# hat.net
KiCad netlist of a schematic drawn in Altium Designer
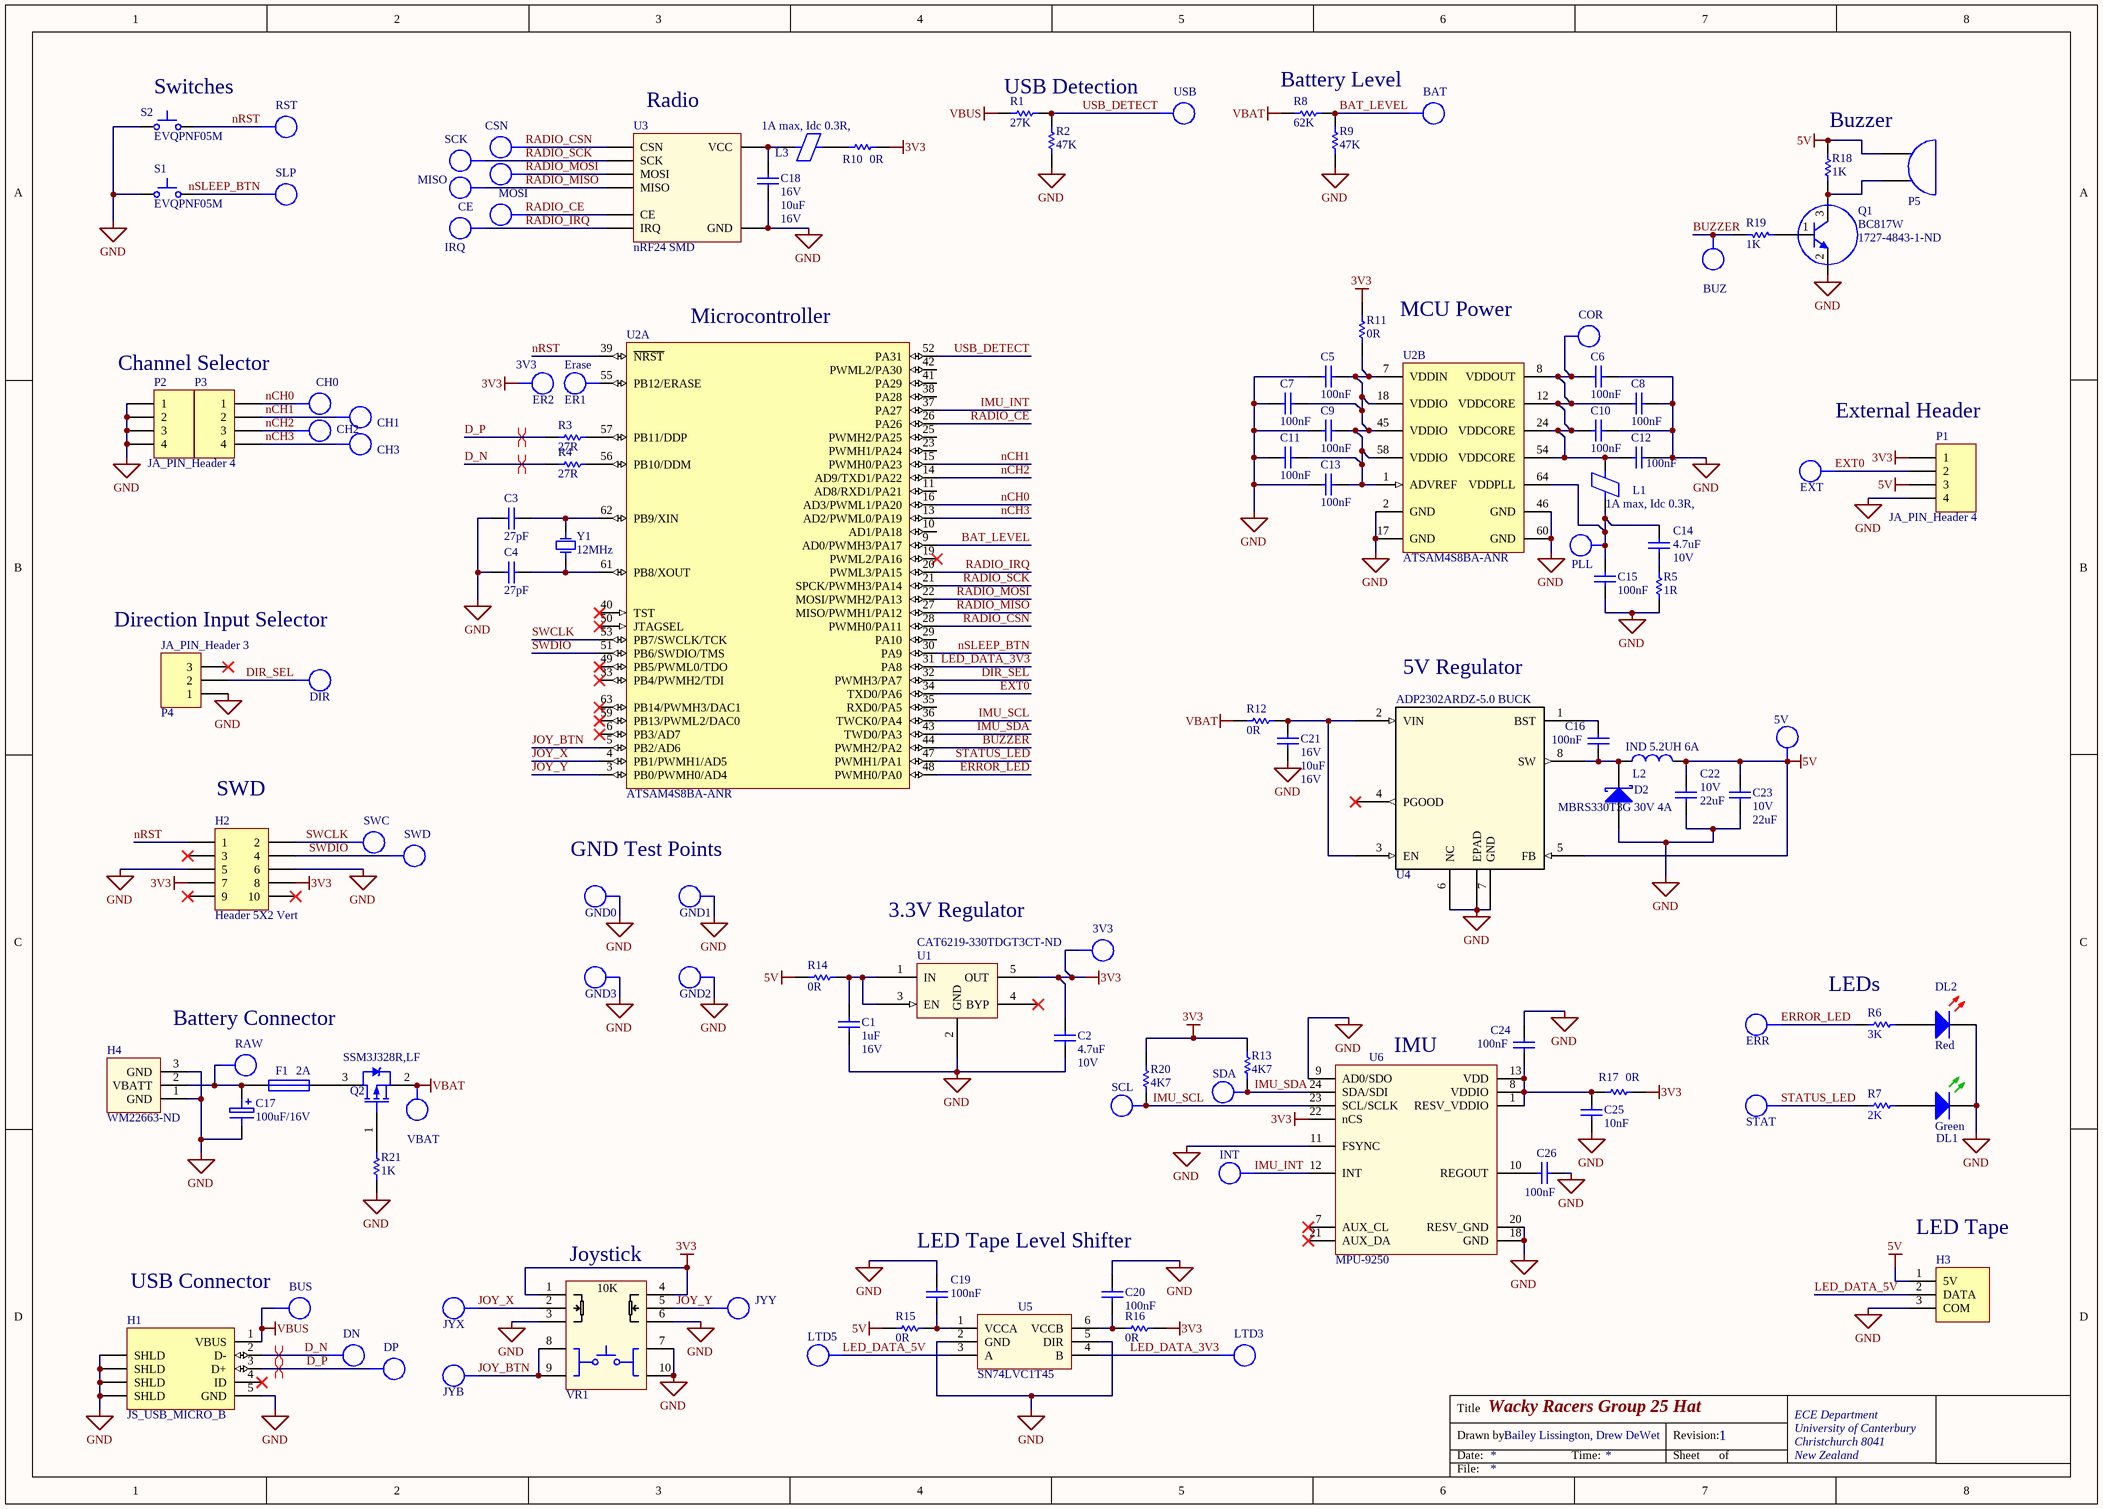
[diagram p0: hat.SchDoc]

(export (version "E")
  (design (tool "Eeschema 10.0.6"))
  (components
    (comp (ref "3V3")
      (value "3V3")
      (footprint "TP_0603")
      (description "Test-Point 3.3x1.6x2.1mm SMD")
      (fields
        (field (name "MANUFACTURER") "Harwin Inc")
        (field (name "MANUFACTURER PART NUMBER") "S1751-46R")
      )
      (libsource (lib "") (part "TP_1206_1"))
    )
    (comp (ref "5V")
      (value "3V3")
      (footprint "TP_0603")
      (description "Test-Point 3.3x1.6x2.1mm SMD")
      (fields
        (field (name "MANUFACTURER") "Harwin Inc")
        (field (name "MANUFACTURER PART NUMBER") "S1751-46R")
      )
      (libsource (lib "") (part "TP_1206_1"))
    )
    (comp (ref "BAT")
      (value "3V3")
      (footprint "TP_0603")
      (description "Test-Point 3.3x1.6x2.1mm SMD")
      (fields
        (field (name "MANUFACTURER") "Harwin Inc")
        (field (name "MANUFACTURER PART NUMBER") "S1751-46R")
      )
      (libsource (lib "") (part "TP_1206_1"))
    )
    (comp (ref "BUS")
      (value "3V3")
      (footprint "TP_0603")
      (description "Test-Point 3.3x1.6x2.1mm SMD")
      (fields
        (field (name "MANUFACTURER") "Harwin Inc")
        (field (name "MANUFACTURER PART NUMBER") "S1751-46R")
      )
      (libsource (lib "") (part "TP_1206_1"))
    )
    (comp (ref "BUZ")
      (value "3V3")
      (footprint "TP_0603")
      (description "Test-Point 3.3x1.6x2.1mm SMD")
      (fields
        (field (name "MANUFACTURER") "Harwin Inc")
        (field (name "MANUFACTURER PART NUMBER") "S1751-46R")
      )
      (libsource (lib "ECE AD19Components_22V1") (part "TP_1206"))
    )
    (comp (ref "C1")
      (value "1uF")
      (footprint "CAPC1608L")
      (description "CAP CER 1uF Y5V -20% +80% 16V 0603")
      (fields (field (name "MAX VOLTAGE") "16V"))
      (libsource (lib "ECE AD19Components_22V1") (part "CC_1uF_0603"))
    )
    (comp (ref "C2")
      (value "4.7uF")
      (footprint "CAPC1608N")
      (description "CAP CER 4.7uF X5R +-20%  10V 0603")
      (fields (field (name "MAX VOLTAGE") "10V"))
      (libsource (lib "ECE AD19Components_22V1") (part "CC_4.7uF_0603"))
    )
    (comp (ref "C3")
      (value "27pF")
      (footprint "CAPC1608L")
      (description "CAP CER 27pF NPO/COG +-5% 50V 0603")
      (libsource (lib "ECE AD19Components_22V1") (part "CC_27pF_0603"))
    )
    (comp (ref "C4")
      (value "27pF")
      (footprint "CAPC1608L")
      (description "CAP CER 27pF NPO/COG +-5% 50V 0603")
      (libsource (lib "ECE AD19Components_22V1") (part "CC_27pF_0603"))
    )
    (comp (ref "C5")
      (value "100nF")
      (footprint "CAPC1608L")
      (description "CAP CER 100nF X7R +-10% 50V 0603")
      (libsource (lib "ECE AD19Components_22V1") (part "CC_100nF_0603"))
    )
    (comp (ref "C6")
      (value "100nF")
      (footprint "CAPC1608L")
      (description "CAP CER 100nF X7R +-10% 50V 0603")
      (libsource (lib "ECE AD19Components_22V1") (part "CC_100nF_0603"))
    )
    (comp (ref "C7")
      (value "100nF")
      (footprint "CAPC1608L")
      (description "CAP CER 100nF X7R +-10% 50V 0603")
      (libsource (lib "ECE AD19Components_22V1") (part "CC_100nF_0603"))
    )
    (comp (ref "C8")
      (value "100nF")
      (footprint "CAPC1608L")
      (description "CAP CER 100nF X7R +-10% 50V 0603")
      (libsource (lib "ECE AD19Components_22V1") (part "CC_100nF_0603"))
    )
    (comp (ref "C9")
      (value "100nF")
      (footprint "CAPC1608L")
      (description "CAP CER 100nF X7R +-10% 50V 0603")
      (libsource (lib "ECE AD19Components_22V1") (part "CC_100nF_0603"))
    )
    (comp (ref "C10")
      (value "100nF")
      (footprint "CAPC1608L")
      (description "CAP CER 100nF X7R +-10% 50V 0603")
      (libsource (lib "ECE AD19Components_22V1") (part "CC_100nF_0603"))
    )
    (comp (ref "C11")
      (value "100nF")
      (footprint "CAPC1608L")
      (description "CAP CER 100nF X7R +-10% 50V 0603")
      (libsource (lib "ECE AD19Components_22V1") (part "CC_100nF_0603"))
    )
    (comp (ref "C12")
      (value "100nF")
      (footprint "CAPC1608L")
      (description "CAP CER 100nF X7R +-10% 50V 0603")
      (libsource (lib "ECE AD19Components_22V1") (part "CC_100nF_0603"))
    )
    (comp (ref "C13")
      (value "100nF")
      (footprint "CAPC1608L")
      (description "CAP CER 100nF X7R +-10% 50V 0603")
      (libsource (lib "ECE AD19Components_22V1") (part "CC_100nF_0603"))
    )
    (comp (ref "C14")
      (value "4.7uF")
      (footprint "CAPC1608N")
      (description "CAP CER 4.7uF X5R +-20%  10V 0603")
      (fields (field (name "MAX VOLTAGE") "10V"))
      (libsource (lib "ECE AD19Components_22V1") (part "CC_4.7uF_0603"))
    )
    (comp (ref "C15")
      (value "100nF")
      (footprint "CAPC1608L")
      (description "CAP CER 100nF X7R +-10% 50V 0603")
      (libsource (lib "ECE AD19Components_22V1") (part "CC_100nF_0603"))
    )
    (comp (ref "C16")
      (value "100nF")
      (footprint "CAPC1608L")
      (description "CAP CER 100nF X7R +-10% 50V 0603")
      (libsource (lib "ECE AD19Components_22V1") (part "CC_100nF_0603"))
    )
    (comp (ref "C17")
      (value "100uF/16V")
      (footprint "NICH-1")
      (description "CAP ALUM 100uF 16V SMD")
      (fields (field (name "MANUFACTURER") "Nichcon"))
      (libsource (lib "ECE AD19Components_22V1") (part "CA_100uF_16V"))
    )
    (comp (ref "C18")
      (value "10uF")
      (footprint "CAPC2012L")
      (description "CAP CER 10uF X5R 16V 0805")
      (fields
        (field (name "MANUFACTURER") "Samsung Electro-Mechanics")
        (field (name "MANUFACTURER PART NUMBER") "CL21A106KOQNNWE")
        (field (name "VOLTAGE - RATED") "16V")
        (field (name "MAX VOLTAGE") "16V")
      )
      (libsource (lib "ECE AD19Components_22V1") (part "CC_10uF_0805_16V"))
    )
    (comp (ref "C19")
      (value "100nF")
      (footprint "CAPC1608L")
      (description "CAP CER 100nF X7R +-10% 50V 0603")
      (libsource (lib "ECE AD19Components_22V1") (part "CC_100nF_0603"))
    )
    (comp (ref "C20")
      (value "100nF")
      (footprint "CAPC1608L")
      (description "CAP CER 100nF X7R +-10% 50V 0603")
      (libsource (lib "ECE AD19Components_22V1") (part "CC_100nF_0603"))
    )
    (comp (ref "C21")
      (value "10uF")
      (footprint "CAPC2012L")
      (description "CAP CER 10uF X5R 16V 0805")
      (fields
        (field (name "MANUFACTURER") "Samsung Electro-Mechanics")
        (field (name "MANUFACTURER PART NUMBER") "CL21A106KOQNNWE")
        (field (name "VOLTAGE - RATED") "16V")
        (field (name "MAX VOLTAGE") "16V")
      )
      (libsource (lib "ECE AD19Components_22V1") (part "CC_10uF_0805_16V"))
    )
    (comp (ref "C22")
      (value "22uF")
      (footprint "CAPC3216L")
      (description "CAP CER 22uF Y5V -20% +80% 10V 1206")
      (fields (field (name "MAX VOLTAGE") "10V"))
      (libsource (lib "ECE AD19Components_22V1") (part "CC_22uF_1206"))
    )
    (comp (ref "C23")
      (value "22uF")
      (footprint "CAPC3216L")
      (description "CAP CER 22uF Y5V -20% +80% 10V 1206")
      (fields (field (name "MAX VOLTAGE") "10V"))
      (libsource (lib "ECE AD19Components_22V1") (part "CC_22uF_1206"))
    )
    (comp (ref "C24")
      (value "100nF")
      (footprint "CAPC1608L")
      (description "CAP CER 100nF X7R +-10% 50V 0603")
      (libsource (lib "ECE AD19Components_22V1") (part "CC_100nF_0603"))
    )
    (comp (ref "C25")
      (value "10nF")
      (footprint "CAPC1608L")
      (description "CAP CER 10nF X7R +-10% 50V 0603")
      (libsource (lib "ECE AD19Components_22V1") (part "CC_10nF_0603"))
    )
    (comp (ref "C26")
      (value "100nF")
      (footprint "CAPC1608L")
      (description "CAP CER 100nF X7R +-10% 50V 0603")
      (libsource (lib "ECE AD19Components_22V1") (part "CC_100nF_0603"))
    )
    (comp (ref "CE")
      (value "3V3")
      (footprint "TP_0603")
      (description "Test-Point 3.3x1.6x2.1mm SMD")
      (fields
        (field (name "MANUFACTURER") "Harwin Inc")
        (field (name "MANUFACTURER PART NUMBER") "S1751-46R")
      )
      (libsource (lib "ECE AD19Components_22V1") (part "TP_1206"))
    )
    (comp (ref "CH0")
      (value "3V3")
      (footprint "TP_0603")
      (description "Test-Point 3.3x1.6x2.1mm SMD")
      (fields
        (field (name "MANUFACTURER") "Harwin Inc")
        (field (name "MANUFACTURER PART NUMBER") "S1751-46R")
      )
      (libsource (lib "ECE AD19Components_22V1") (part "TP_1206"))
    )
    (comp (ref "CH1")
      (value "3V3")
      (footprint "TP_0603")
      (description "Test-Point 3.3x1.6x2.1mm SMD")
      (fields
        (field (name "MANUFACTURER") "Harwin Inc")
        (field (name "MANUFACTURER PART NUMBER") "S1751-46R")
      )
      (libsource (lib "ECE AD19Components_22V1") (part "TP_1206"))
    )
    (comp (ref "CH2")
      (value "3V3")
      (footprint "TP_0603")
      (description "Test-Point 3.3x1.6x2.1mm SMD")
      (fields
        (field (name "MANUFACTURER") "Harwin Inc")
        (field (name "MANUFACTURER PART NUMBER") "S1751-46R")
      )
      (libsource (lib "ECE AD19Components_22V1") (part "TP_1206"))
    )
    (comp (ref "CH3")
      (value "3V3")
      (footprint "TP_0603")
      (description "Test-Point 3.3x1.6x2.1mm SMD")
      (fields
        (field (name "MANUFACTURER") "Harwin Inc")
        (field (name "MANUFACTURER PART NUMBER") "S1751-46R")
      )
      (libsource (lib "ECE AD19Components_22V1") (part "TP_1206"))
    )
    (comp (ref "COR")
      (value "3V3")
      (footprint "TP_0603")
      (description "Test-Point 3.3x1.6x2.1mm SMD")
      (fields
        (field (name "MANUFACTURER") "Harwin Inc")
        (field (name "MANUFACTURER PART NUMBER") "S1751-46R")
      )
      (libsource (lib "") (part "TP_1206_1"))
    )
    (comp (ref "CSN")
      (value "3V3")
      (footprint "TP_0603")
      (description "Test-Point 3.3x1.6x2.1mm SMD")
      (fields
        (field (name "MANUFACTURER") "Harwin Inc")
        (field (name "MANUFACTURER PART NUMBER") "S1751-46R")
      )
      (libsource (lib "ECE AD19Components_22V1") (part "TP_1206"))
    )
    (comp (ref "D2")
      (value "MBRS330T3G 30V 4A")
      (footprint "SMC")
      (description "SCHOTTKY  30V 4A")
      (fields
        (field (name "MANUFACTURER") "ON Semiconductor")
        (field (name "MANUFACTURER PART NUMBER") "MBRS330T3G")
      )
      (libsource (lib "ENCE461AD19_V22") (part "MBRS330T3G"))
    )
    (comp (ref "DIR")
      (value "3V3")
      (footprint "TP_0603")
      (description "Test-Point 3.3x1.6x2.1mm SMD")
      (fields
        (field (name "MANUFACTURER") "Harwin Inc")
        (field (name "MANUFACTURER PART NUMBER") "S1751-46R")
      )
      (libsource (lib "ECE AD19Components_22V1") (part "TP_1206"))
    )
    (comp (ref "DL1")
      (value "Green")
      (footprint "WL-SMCW0603")
      (description "LED Green 430mcd 0603 SMD")
      (fields
        (field (name "MANUFACTURER") "WURTH ELEKTRONIK")
        (field (name "MANUFACTURER PART NUMBER") "150060GS75000")
        (field (name "LED COLOUR") "Green")
      )
      (libsource (lib "ECE AD19Components_22V1") (part "DL_150060GS75000"))
    )
    (comp (ref "DL2")
      (value "Red")
      (footprint "WL-SMCW0603")
      (description "LED Red 250mcd 0603 SMD")
      (fields
        (field (name "MANUFACTURER") "WURTH ELEKTRONIK")
        (field (name "MANUFACTURER PART NUMBER") "150060RS75000")
        (field (name "LED COLOUR") "Red")
      )
      (libsource (lib "ECE AD19Components_22V1") (part "DL_150060RS75000"))
    )
    (comp (ref "DN")
      (value "3V3")
      (footprint "TP_0603")
      (description "Test-Point 3.3x1.6x2.1mm SMD")
      (fields
        (field (name "MANUFACTURER") "Harwin Inc")
        (field (name "MANUFACTURER PART NUMBER") "S1751-46R")
      )
      (libsource (lib "") (part "TP_1206_1"))
    )
    (comp (ref "DP")
      (value "3V3")
      (footprint "TP_0603")
      (description "Test-Point 3.3x1.6x2.1mm SMD")
      (fields
        (field (name "MANUFACTURER") "Harwin Inc")
        (field (name "MANUFACTURER PART NUMBER") "S1751-46R")
      )
      (libsource (lib "") (part "TP_1206_1"))
    )
    (comp (ref "ER1")
      (value "Erase")
      (footprint "TP_0603")
      (description "Test-Point 3.3x1.6x2.1mm SMD")
      (fields
        (field (name "MANUFACTURER") "Harwin Inc")
        (field (name "MANUFACTURER PART NUMBER") "S1751-46R")
      )
      (libsource (lib "") (part "TP_1206_1"))
    )
    (comp (ref "ER2")
      (value "3V3")
      (footprint "TP_0603")
      (description "Test-Point 3.3x1.6x2.1mm SMD")
      (fields
        (field (name "MANUFACTURER") "Harwin Inc")
        (field (name "MANUFACTURER PART NUMBER") "S1751-46R")
      )
      (libsource (lib "") (part "TP_1206_1"))
    )
    (comp (ref "ERR")
      (value "3V3")
      (footprint "TP_0603")
      (description "Test-Point 3.3x1.6x2.1mm SMD")
      (fields
        (field (name "MANUFACTURER") "Harwin Inc")
        (field (name "MANUFACTURER PART NUMBER") "S1751-46R")
      )
      (libsource (lib "ECE AD19Components_22V1") (part "TP_1206"))
    )
    (comp (ref "EXT")
      (value "3V3")
      (footprint "TP_0603")
      (description "Test-Point 3.3x1.6x2.1mm SMD")
      (fields
        (field (name "MANUFACTURER") "Harwin Inc")
        (field (name "MANUFACTURER PART NUMBER") "S1751-46R")
      )
      (libsource (lib "") (part "TP_1206_1"))
    )
    (comp (ref "F1")
      (value "2A")
      (footprint "RESC3216N")
      (description "Fuse 2.0A Very Fast Acting 1206 SMD")
      (fields
        (field (name "MANUFACTURER") "MULTICOMP")
        (field (name "MANUFACTURER PART NUMBER") "MC12CF 002")
      )
      (libsource (lib "ECE AD19Components_22V1") (part "FS_Fuse_2.0A"))
    )
    (comp (ref "GND0")
      (value "TP")
      (footprint "TP_1206")
      (description "Test-Point 3.3x1.6x2.1mm SMD")
      (fields
        (field (name "MANUFACTURER") "Harwin Inc")
        (field (name "MANUFACTURER PART NUMBER") "S1751-46R")
      )
      (libsource (lib "") (part "TP_1206_1"))
    )
    (comp (ref "GND1")
      (value "TP")
      (footprint "TP_1206")
      (description "Test-Point 3.3x1.6x2.1mm SMD")
      (fields
        (field (name "MANUFACTURER") "Harwin Inc")
        (field (name "MANUFACTURER PART NUMBER") "S1751-46R")
      )
      (libsource (lib "") (part "TP_1206_1"))
    )
    (comp (ref "GND2")
      (value "TP")
      (footprint "TP_1206")
      (description "Test-Point 3.3x1.6x2.1mm SMD")
      (fields
        (field (name "MANUFACTURER") "Harwin Inc")
        (field (name "MANUFACTURER PART NUMBER") "S1751-46R")
      )
      (libsource (lib "") (part "TP_1206_1"))
    )
    (comp (ref "GND3")
      (value "TP")
      (footprint "TP_1206")
      (description "Test-Point 3.3x1.6x2.1mm SMD")
      (fields
        (field (name "MANUFACTURER") "Harwin Inc")
        (field (name "MANUFACTURER PART NUMBER") "S1751-46R")
      )
      (libsource (lib "") (part "TP_1206_1"))
    )
    (comp (ref "H1")
      (value "JS_USB_MICRO_B")
      (footprint "FCI_USB_10118194-0001LF")
      (description "CONN USB MICRO B RECPT SMT R/A")
      (fields (field (name "MANUFACTURER") "FCI") (field (name "MANUFACTURER PART NUMBER") "10118194-0001LF"))
      (libsource (lib "ECE AD19Components_22V1") (part "JS_USB_MICRO_B_SMT"))
    )
    (comp (ref "H2")
      (value "Header 5X2 Vert")
      (footprint "IDC2.54-V10D")
      (description "IDC Header, 2,54mm, 10-Pin, Vert")
      (libsource (lib "ECE AD19Components_22V1") (part "JA_HDR_IDC_5X2_VERT"))
    )
    (comp (ref "H3")
      (value "3 Pin Molex KK Hdr")
      (footprint "MOLEX_KK_3_HDR")
      (description "CONN HEADER 3POS 2.54mm VERT_Thru Hole")
      (fields (field (name "MANUFACTURER") "Molex"))
      (libsource (lib "ENCE461AD19_V22") (part "LED_Strip_Header"))
    )
    (comp (ref "H4")
      (value "Battery_HEADER_3pin")
      (footprint "BATT_HEADER_3POS")
      (description "3Pin Header 2.54mm spacing\r\nDigikey #WM22663-ND")
      (fields (field (name "SUPPLIER PART NUMBER 1") "WM22663-ND"))
      (libsource (lib "ENCE461AD19_V22") (part "Battery_HEADER_3pin"))
    )
    (comp (ref "INT")
      (value "3V3")
      (footprint "TP_0603")
      (description "Test-Point 3.3x1.6x2.1mm SMD")
      (fields
        (field (name "MANUFACTURER") "Harwin Inc")
        (field (name "MANUFACTURER PART NUMBER") "S1751-46R")
      )
      (libsource (lib "ECE AD19Components_22V1") (part "TP_1206"))
    )
    (comp (ref "IRQ")
      (value "3V3")
      (footprint "TP_0603")
      (description "Test-Point 3.3x1.6x2.1mm SMD")
      (fields
        (field (name "MANUFACTURER") "Harwin Inc")
        (field (name "MANUFACTURER PART NUMBER") "S1751-46R")
      )
      (libsource (lib "ECE AD19Components_22V1") (part "TP_1206"))
    )
    (comp (ref "JYB")
      (value "3V3")
      (footprint "TP_0603")
      (description "Test-Point 3.3x1.6x2.1mm SMD")
      (fields
        (field (name "MANUFACTURER") "Harwin Inc")
        (field (name "MANUFACTURER PART NUMBER") "S1751-46R")
      )
      (libsource (lib "") (part "TP_1206_1"))
    )
    (comp (ref "JYX")
      (value "3V3")
      (footprint "TP_0603")
      (description "Test-Point 3.3x1.6x2.1mm SMD")
      (fields
        (field (name "MANUFACTURER") "Harwin Inc")
        (field (name "MANUFACTURER PART NUMBER") "S1751-46R")
      )
      (libsource (lib "") (part "TP_1206_1"))
    )
    (comp (ref "JYY")
      (value "3V3")
      (footprint "TP_0603")
      (description "Test-Point 3.3x1.6x2.1mm SMD")
      (fields
        (field (name "MANUFACTURER") "Harwin Inc")
        (field (name "MANUFACTURER PART NUMBER") "S1751-46R")
      )
      (libsource (lib "ECE AD19Components_22V1") (part "TP_1206"))
    )
    (comp (ref "L1")
      (value "1A max, Idc 0.3R,")
      (footprint "INDC3216L")
      (description "Ferrite Bead, Rdc 0.3R, Z100MHZ 600R, Imax 1A, SMD 1206")
      (fields
        (field (name "MANUFACTURER") "FAIR-RITE")
        (field (name "MANUFACTURER PART NUMBER") "2512066017Y1")
      )
      (libsource (lib "ECE AD19Components_22V1") (part "IN_Ferrite-Bead"))
    )
    (comp (ref "L2")
      (value "IND 5.2UH 6A")
      (footprint "INDUCTOR5u2")
      (description "FIXED IND 5.2UH 6A 22 MOHM SMD")
      (fields
        (field (name "MANUFACTURER") "Sumida America Components Inc.")
        (field (name "MANUFACTURER PART NUMBER") "CDRH104RNP-5R2NC")
      )
      (libsource (lib "ENCE461AD19_V22") (part "CDRH104RNP-5R2NC"))
    )
    (comp (ref "L3")
      (value "1A max, Idc 0.3R,")
      (footprint "INDC3216L")
      (description "Ferrite Bead, Rdc 0.3R, Z100MHZ 600R, Imax 1A, SMD 1206")
      (fields
        (field (name "MANUFACTURER") "FAIR-RITE")
        (field (name "MANUFACTURER PART NUMBER") "2512066017Y1")
      )
      (libsource (lib "ECE AD19Components_22V1") (part "IN_Ferrite-Bead"))
    )
    (comp (ref "LTD3")
      (value "3V3")
      (footprint "TP_0603")
      (description "Test-Point 3.3x1.6x2.1mm SMD")
      (fields
        (field (name "MANUFACTURER") "Harwin Inc")
        (field (name "MANUFACTURER PART NUMBER") "S1751-46R")
      )
      (libsource (lib "") (part "TP_1206_1"))
    )
    (comp (ref "LTD5")
      (value "3V3")
      (footprint "TP_0603")
      (description "Test-Point 3.3x1.6x2.1mm SMD")
      (fields
        (field (name "MANUFACTURER") "Harwin Inc")
        (field (name "MANUFACTURER PART NUMBER") "S1751-46R")
      )
      (libsource (lib "ECE AD19Components_22V1") (part "TP_1206"))
    )
    (comp (ref "MISO")
      (value "3V3")
      (footprint "TP_0603")
      (description "Test-Point 3.3x1.6x2.1mm SMD")
      (fields
        (field (name "MANUFACTURER") "Harwin Inc")
        (field (name "MANUFACTURER PART NUMBER") "S1751-46R")
      )
      (libsource (lib "ECE AD19Components_22V1") (part "TP_1206"))
    )
    (comp (ref "MOSI")
      (value "3V3")
      (footprint "TP_0603")
      (description "Test-Point 3.3x1.6x2.1mm SMD")
      (fields
        (field (name "MANUFACTURER") "Harwin Inc")
        (field (name "MANUFACTURER PART NUMBER") "S1751-46R")
      )
      (libsource (lib "ECE AD19Components_22V1") (part "TP_1206"))
    )
    (comp (ref "P1")
      (value "JA_PIN_Header 4")
      (footprint "HDR1X4")
      (description "Header, 4-Pin")
      (fields (field (name "PUBLISHER") "Altium Limited"))
      (libsource (lib "") (part "JA_PIN_Header 4_1"))
    )
    (comp (ref "P2")
      (value "JA_PIN_Header 4")
      (footprint "HDR1X4")
      (description "Header, 4-Pin")
      (fields (field (name "PUBLISHER") "Altium Limited"))
      (libsource (lib "") (part "JA_PIN_Header 4_1"))
    )
    (comp (ref "P3")
      (value "JA_PIN_Header 4")
      (footprint "HDR1X4")
      (description "Header, 4-Pin")
      (fields (field (name "PUBLISHER") "Altium Limited"))
      (libsource (lib "ECE AD19Components_22V1") (part "JA_PIN_Header 4"))
    )
    (comp (ref "P4")
      (value "JA_PIN_Header 3")
      (footprint "HDR1X3")
      (description "Header, 3-Pin")
      (fields (field (name "PUBLISHER") "Altium Limited"))
      (libsource (lib "ECE AD19Components_22V1") (part "JA_PIN_Header 3"))
    )
    (comp (ref "P5")
      (value "Piezo Buzzer")
      (footprint "BUZZER")
      (description "TDK - PS1240P02BT - BUZZER, PIEZO, 70DB, 12.2MM")
      (libsource (lib "ENCE461AD19_V22") (part "Piezo Buzzer"))
    )
    (comp (ref "PLL")
      (value "3V3")
      (footprint "TP_0603")
      (description "Test-Point 3.3x1.6x2.1mm SMD")
      (fields
        (field (name "MANUFACTURER") "Harwin Inc")
        (field (name "MANUFACTURER PART NUMBER") "S1751-46R")
      )
      (libsource (lib "") (part "TP_1206_1"))
    )
    (comp (ref "Q1")
      (value "BC817W")
      (footprint "SOT323_M")
      (description "NPN GP Bipolar Transistor 45V 500mA SOT323")
      (fields (field (name "MANUFACTURER") "NXP") (field (name "SUPPLIER PART NUMBER 2") "1727-4843-1-ND"))
      (libsource (lib "ECE AD19Components_22V1") (part "TB_BC817W"))
    )
    (comp (ref "Q2")
      (value "SSM3J328R,LF")
      (footprint "SOT23_L")
      (description "MOSFET P-CH 20V 6A SOT23-3")
      (fields
        (field (name "MANUFACTURER") "Toshiba")
        (field (name "MANUFACTURER PART NUMBER") "SSM3J328R,LF")
      )
      (libsource (lib "ECE AD19Components_22V1") (part "TM_SSM3J328R"))
    )
    (comp (ref "R1")
      (value "27K")
      (footprint "RESC1608L")
      (description "RES 27K OHM 1/10W 5% 0603 SMD")
      (libsource (lib "ECE AD19Components_22V1") (part "RS_27K"))
    )
    (comp (ref "R2")
      (value "47K")
      (footprint "RESC1608N")
      (description "RES 47.0K OHM 1/10W 5% 0603 SMD")
      (libsource (lib "ECE AD19Components_22V1") (part "RS_47K"))
    )
    (comp (ref "R3")
      (value "27R")
      (footprint "RESC1608L")
      (description "RES 27 OHM 1/10W 5% 0603 SMD")
      (libsource (lib "ECE AD19Components_22V1") (part "RS_27R"))
    )
    (comp (ref "R4")
      (value "27R")
      (footprint "RESC1608L")
      (description "RES 27 OHM 1/10W 5% 0603 SMD")
      (libsource (lib "ECE AD19Components_22V1") (part "RS_27R"))
    )
    (comp (ref "R5")
      (value "1R")
      (footprint "RESC3216L")
      (description "RES 1R OHM 1/4W 5% 1206 SMD")
      (libsource (lib "ECE AD19Components_22V1") (part "RT_1R"))
    )
    (comp (ref "R6")
      (value "3K")
      (footprint "RESC1608L")
      (description "RES 3K OHM 1/10W 5% 0603 SMD")
      (libsource (lib "ECE AD19Components_22V1") (part "RS_3K"))
    )
    (comp (ref "R7")
      (value "2K")
      (footprint "RESC1608L")
      (description "RES 2K OHM 1/10W 5% 0603 SMD")
      (libsource (lib "ECE AD19Components_22V1") (part "RS_2K"))
    )
    (comp (ref "R8")
      (value "62K")
      (footprint "RESC1608L")
      (description "RES 62.0K OHM 1/10W 5% 0603 SMD")
      (libsource (lib "ECE AD19Components_22V1") (part "RS_62K"))
    )
    (comp (ref "R9")
      (value "47K")
      (footprint "RESC1608N")
      (description "RES 47.0K OHM 1/10W 5% 0603 SMD")
      (libsource (lib "ECE AD19Components_22V1") (part "RS_47K"))
    )
    (comp (ref "R10")
      (value "0R")
      (footprint "RESC1608L")
      (description "RES 0.0 OHM 1/10W 5% 0603 SMD")
      (libsource (lib "ECE AD19Components_22V1") (part "RS_0R0"))
    )
    (comp (ref "R11")
      (value "0R")
      (footprint "RESC1608L")
      (description "RES 0.0 OHM 1/10W 5% 0603 SMD")
      (libsource (lib "ECE AD19Components_22V1") (part "RS_0R0"))
    )
    (comp (ref "R12")
      (value "0R")
      (footprint "RESC1608L")
      (description "RES 0.0 OHM 1/10W 5% 0603 SMD")
      (libsource (lib "ECE AD19Components_22V1") (part "RS_0R0"))
    )
    (comp (ref "R13")
      (value "4K7")
      (footprint "RESC1608L")
      (description "RES 4.7K OHM 1/10W 5% 0603 SMD")
      (libsource (lib "ECE AD19Components_22V1") (part "RS_4K7"))
    )
    (comp (ref "R14")
      (value "0R")
      (footprint "RESC1608L")
      (description "RES 0.0 OHM 1/10W 5% 0603 SMD")
      (libsource (lib "ECE AD19Components_22V1") (part "RS_0R0"))
    )
    (comp (ref "R15")
      (value "0R")
      (footprint "RESC1608L")
      (description "RES 0.0 OHM 1/10W 5% 0603 SMD")
      (libsource (lib "ECE AD19Components_22V1") (part "RS_0R0"))
    )
    (comp (ref "R16")
      (value "0R")
      (footprint "RESC1608L")
      (description "RES 0.0 OHM 1/10W 5% 0603 SMD")
      (libsource (lib "ECE AD19Components_22V1") (part "RS_0R0"))
    )
    (comp (ref "R17")
      (value "0R")
      (footprint "RESC1608L")
      (description "RES 0.0 OHM 1/10W 5% 0603 SMD")
      (libsource (lib "ECE AD19Components_22V1") (part "RS_0R0"))
    )
    (comp (ref "R18")
      (value "1K")
      (footprint "RESC1608L")
      (description "RES 1.0K OHM 1/10W 5% 0603 SMD")
      (libsource (lib "ECE AD19Components_22V1") (part "RS_1K"))
    )
    (comp (ref "R19")
      (value "1K")
      (footprint "RESC1608L")
      (description "RES 1.0K OHM 1/10W 5% 0603 SMD")
      (libsource (lib "ECE AD19Components_22V1") (part "RS_1K"))
    )
    (comp (ref "R20")
      (value "4K7")
      (footprint "RESC1608L")
      (description "RES 4.7K OHM 1/10W 5% 0603 SMD")
      (libsource (lib "ECE AD19Components_22V1") (part "RS_4K7"))
    )
    (comp (ref "R21")
      (value "1K")
      (footprint "RESC1608L")
      (description "RES 1.0K OHM 1/10W 5% 0603 SMD")
      (libsource (lib "ECE AD19Components_22V1") (part "RS_1K"))
    )
    (comp (ref "RAW")
      (value "3V3")
      (footprint "TP_0603")
      (description "Test-Point 3.3x1.6x2.1mm SMD")
      (fields
        (field (name "MANUFACTURER") "Harwin Inc")
        (field (name "MANUFACTURER PART NUMBER") "S1751-46R")
      )
      (libsource (lib "") (part "TP_1206_1"))
    )
    (comp (ref "RST")
      (value "3V3")
      (footprint "TP_0603")
      (description "Test-Point 3.3x1.6x2.1mm SMD")
      (fields
        (field (name "MANUFACTURER") "Harwin Inc")
        (field (name "MANUFACTURER PART NUMBER") "S1751-46R")
      )
      (libsource (lib "") (part "TP_1206_1"))
    )
    (comp (ref "S1")
      (value "EVQPNF05M")
      (footprint "EVQPNF05M")
      (description "Panasonic 6 x 3.5mm SMD Light Touch Switch Type SMD")
      (fields (field (name "MANUFACTURER") "Panasonic"))
      (libsource (lib "ECE AD19Components_22V1") (part "WS_EVQPNF05M"))
    )
    (comp (ref "S2")
      (value "EVQPNF05M")
      (footprint "EVQPNF05M")
      (description "Panasonic 6 x 3.5mm SMD Light Touch Switch Type SMD")
      (fields (field (name "MANUFACTURER") "Panasonic"))
      (libsource (lib "ECE AD19Components_22V1") (part "WS_EVQPNF05M"))
    )
    (comp (ref "SCK")
      (value "3V3")
      (footprint "TP_0603")
      (description "Test-Point 3.3x1.6x2.1mm SMD")
      (fields
        (field (name "MANUFACTURER") "Harwin Inc")
        (field (name "MANUFACTURER PART NUMBER") "S1751-46R")
      )
      (libsource (lib "ECE AD19Components_22V1") (part "TP_1206"))
    )
    (comp (ref "SCL")
      (value "3V3")
      (footprint "TP_0603")
      (description "Test-Point 3.3x1.6x2.1mm SMD")
      (fields
        (field (name "MANUFACTURER") "Harwin Inc")
        (field (name "MANUFACTURER PART NUMBER") "S1751-46R")
      )
      (libsource (lib "ECE AD19Components_22V1") (part "TP_1206"))
    )
    (comp (ref "SDA")
      (value "3V3")
      (footprint "TP_0603")
      (description "Test-Point 3.3x1.6x2.1mm SMD")
      (fields
        (field (name "MANUFACTURER") "Harwin Inc")
        (field (name "MANUFACTURER PART NUMBER") "S1751-46R")
      )
      (libsource (lib "ECE AD19Components_22V1") (part "TP_1206"))
    )
    (comp (ref "SLP")
      (value "3V3")
      (footprint "TP_0603")
      (description "Test-Point 3.3x1.6x2.1mm SMD")
      (fields
        (field (name "MANUFACTURER") "Harwin Inc")
        (field (name "MANUFACTURER PART NUMBER") "S1751-46R")
      )
      (libsource (lib "") (part "TP_1206_1"))
    )
    (comp (ref "STAT")
      (value "3V3")
      (footprint "TP_0603")
      (description "Test-Point 3.3x1.6x2.1mm SMD")
      (fields
        (field (name "MANUFACTURER") "Harwin Inc")
        (field (name "MANUFACTURER PART NUMBER") "S1751-46R")
      )
      (libsource (lib "ECE AD19Components_22V1") (part "TP_1206"))
    )
    (comp (ref "SWC")
      (value "3V3")
      (footprint "TP_0603")
      (description "Test-Point 3.3x1.6x2.1mm SMD")
      (fields
        (field (name "MANUFACTURER") "Harwin Inc")
        (field (name "MANUFACTURER PART NUMBER") "S1751-46R")
      )
      (libsource (lib "") (part "TP_1206_1"))
    )
    (comp (ref "SWD")
      (value "3V3")
      (footprint "TP_0603")
      (description "Test-Point 3.3x1.6x2.1mm SMD")
      (fields
        (field (name "MANUFACTURER") "Harwin Inc")
        (field (name "MANUFACTURER PART NUMBER") "S1751-46R")
      )
      (libsource (lib "") (part "TP_1206_1"))
    )
    (comp (ref "U1")
      (value "CAT6219-330TDGT3")
      (footprint "SOT95P280X145-5N")
      (description "IC REG LIN 3.3V 500MA TSOT23-5")
      (fields
        (field (name "BASE PART NUMBER") "CAT6219")
        (field (name "SUPPLIER PART NUMBER") "CAT6219-330TDGT3CT-ND")
      )
      (libsource (lib "ENCE461AD19_V22") (part "SV_CAT6219-330TDGT3"))
    )
    (comp (ref "U2")
      (value "ATSAM4S8BA-ANR")
      (footprint "LQFP64_L")
      (description "IC MCU 32BIT 512KB FLASH 64LQFP")
      (fields (field (name "MANUFACTURER") "Atmel"))
      (libsource (lib "ECE AD19Components_22V1") (part "SE_ATSAM4S16BA-MU"))
    )
    (comp (ref "U3")
      (value "nRF24 SMD")
      (footprint "NRF24")
      (description "nRF24 SMD Module")
      (libsource (lib "ENCE461AD19_V22") (part "NRF24"))
    )
    (comp (ref "U4")
      (value "ADP2302ARDZ-5.0 BUCK")
      (footprint "RD_8_1")
      (description "IC REG BUCK 5V 2A 8SOIC")
      (fields (field (name "MANUFACTURER_PART_NUMBER") "ADP2302ARDZ-5.0-R7"))
      (libsource (lib "ENCE461AD19_V22") (part "ADP2302ARDZ-5.0-R7"))
    )
    (comp (ref "U5")
      (value "SN74LVC1T45")
      (footprint "SOT23-6_N")
      (description "1.8V - 5V level converter")
      (libsource (lib "ENCE461AD19_V22") (part "SN74LVC1T45"))
    )
    (comp (ref "U6")
      (value "MPU-9250")
      (footprint "Quad24")
      (description "9 axis IMU")
      (libsource (lib "ENCE461AD19_V22") (part "MPU-9250"))
    )
    (comp (ref "USB")
      (value "3V3")
      (footprint "TP_0603")
      (description "Test-Point 3.3x1.6x2.1mm SMD")
      (fields
        (field (name "MANUFACTURER") "Harwin Inc")
        (field (name "MANUFACTURER PART NUMBER") "S1751-46R")
      )
      (libsource (lib "") (part "TP_1206_1"))
    )
    (comp (ref "VBAT")
      (value "3V3")
      (footprint "TP_0603")
      (description "Test-Point 3.3x1.6x2.1mm SMD")
      (fields
        (field (name "MANUFACTURER") "Harwin Inc")
        (field (name "MANUFACTURER PART NUMBER") "S1751-46R")
      )
      (libsource (lib "") (part "TP_1206_1"))
    )
    (comp (ref "VR1")
      (value "Joystick 10k with Sw")
      (footprint "Joystick_Sw")
      (description "JOYSTICK 10K OHM 2 AXIS TH")
      (libsource (lib "ENCE461AD19_V22") (part "Joystick 10k with Sw"))
    )
    (comp (ref "Y1")
      (value "12MHz")
      (footprint "6.0X3.5-4")
      (description "CRYSTAL 12MHZ 18PF 6X3.5mm SMD")
      (fields
        (field (name "MANUFACTURER") "CTS-Frequency Controls")
        (field (name "MANUFACTURER PART NUMBER") "406C35D12M00000")
        (field (name "FREQUENCY") "12MHz")
      )
      (libsource (lib "ECE AD19Components_22V1") (part "XT_CRYSTAL_12MHz_18pF"))
    )
  )
  (nets
    (net (code "1") (name "/BAT_LEVEL") (class "Default")
      (node (ref "BAT") (pin "1") (pinfunction "1_1") (pintype "passive"))
      (node (ref "R8") (pin "1") (pinfunction "1_1") (pintype "passive"))
      (node (ref "R9") (pin "2") (pinfunction "2_2") (pintype "passive"))
      (node (ref "U2") (pin "9") (pinfunction "AD0/PWMH3/PA17_9") (pintype "bidirectional"))
    )
    (net (code "2") (name "/BUZZER") (class "Default")
      (node (ref "BUZ") (pin "1") (pinfunction "1_1") (pintype "passive"))
      (node (ref "R19") (pin "2") (pinfunction "2_2") (pintype "passive"))
      (node (ref "U2") (pin "44") (pinfunction "PWMH2/PA2_44") (pintype "bidirectional"))
    )
    (net (code "3") (name "/DIR_SEL") (class "Default")
      (node (ref "DIR") (pin "1") (pinfunction "1_1") (pintype "passive"))
      (node (ref "P4") (pin "2") (pinfunction "2_2") (pintype "passive"))
      (node (ref "U2") (pin "32") (pinfunction "PWMH3/PA7_32") (pintype "bidirectional"))
    )
    (net (code "4") (name "/D_N") (class "Default")
      (node (ref "DN") (pin "1") (pinfunction "1_1") (pintype "passive"))
      (node (ref "H1") (pin "2") (pinfunction "D-_2") (pintype "bidirectional"))
      (node (ref "R4") (pin "1") (pinfunction "1_1") (pintype "passive"))
    )
    (net (code "5") (name "/D_P") (class "Default")
      (node (ref "DP") (pin "1") (pinfunction "1_1") (pintype "passive"))
      (node (ref "H1") (pin "3") (pinfunction "D+_3") (pintype "bidirectional"))
      (node (ref "R3") (pin "1") (pinfunction "1_1") (pintype "passive"))
    )
    (net (code "6") (name "/ERROR_LED") (class "Default")
      (node (ref "ERR") (pin "1") (pinfunction "1_1") (pintype "passive"))
      (node (ref "R6") (pin "1") (pinfunction "1_1") (pintype "passive"))
      (node (ref "U2") (pin "48") (pinfunction "PWMH0/PA0_48") (pintype "bidirectional"))
    )
    (net (code "7") (name "/EXT0") (class "Default")
      (node (ref "EXT") (pin "1") (pinfunction "1_1") (pintype "passive"))
      (node (ref "P1") (pin "2") (pinfunction "2_2") (pintype "passive"))
      (node (ref "U2") (pin "34") (pinfunction "TXD0/PA6_34") (pintype "bidirectional"))
    )
    (net (code "8") (name "/IMU_INT") (class "Default")
      (node (ref "INT") (pin "1") (pinfunction "1_1") (pintype "passive"))
      (node (ref "U2") (pin "37") (pinfunction "PA27_37") (pintype "bidirectional"))
      (node (ref "U6") (pin "12") (pinfunction "INT_12") (pintype "passive"))
    )
    (net (code "9") (name "/IMU_SCL") (class "Default")
      (node (ref "R20") (pin "1") (pinfunction "1_1") (pintype "passive"))
      (node (ref "SCL") (pin "1") (pinfunction "1_1") (pintype "passive"))
      (node (ref "U2") (pin "36") (pinfunction "TWCK0/PA4_36") (pintype "bidirectional"))
      (node (ref "U6") (pin "23") (pinfunction "SCL/SCLK_23") (pintype "passive"))
    )
    (net (code "10") (name "/IMU_SDA") (class "Default")
      (node (ref "R13") (pin "1") (pinfunction "1_1") (pintype "passive"))
      (node (ref "SDA") (pin "1") (pinfunction "1_1") (pintype "passive"))
      (node (ref "U2") (pin "43") (pinfunction "TWD0/PA3_43") (pintype "bidirectional"))
      (node (ref "U6") (pin "24") (pinfunction "SDA/SDI_24") (pintype "passive"))
    )
    (net (code "11") (name "/JOY_BTN") (class "Default")
      (node (ref "JYB") (pin "1") (pinfunction "1_1") (pintype "passive"))
      (node (ref "U2") (pin "5") (pinfunction "PB2/AD6_5") (pintype "bidirectional"))
      (node (ref "VR1") (pin "8") (pinfunction "8_8") (pintype "passive"))
      (node (ref "VR1") (pin "9") (pinfunction "9_9") (pintype "passive"))
    )
    (net (code "12") (name "/JOY_X") (class "Default")
      (node (ref "JYX") (pin "1") (pinfunction "1_1") (pintype "passive"))
      (node (ref "U2") (pin "4") (pinfunction "PB1/PWMH1/AD5_4") (pintype "bidirectional"))
      (node (ref "VR1") (pin "2") (pinfunction "2_2") (pintype "passive"))
    )
    (net (code "13") (name "/JOY_Y") (class "Default")
      (node (ref "JYY") (pin "1") (pinfunction "1_1") (pintype "passive"))
      (node (ref "U2") (pin "3") (pinfunction "PB0/PWMH0/AD4_3") (pintype "bidirectional"))
      (node (ref "VR1") (pin "5") (pinfunction "2'_5") (pintype "passive"))
    )
    (net (code "14") (name "/LED_DATA_3V3") (class "Default")
      (node (ref "LTD3") (pin "1") (pinfunction "1_1") (pintype "passive"))
      (node (ref "U2") (pin "31") (pinfunction "PA8_31") (pintype "bidirectional"))
      (node (ref "U5") (pin "4") (pinfunction "B_4") (pintype "passive"))
    )
    (net (code "15") (name "/LED_DATA_5V") (class "Default")
      (node (ref "H3") (pin "2") (pinfunction "DATA_2") (pintype "passive"))
      (node (ref "LTD5") (pin "1") (pinfunction "1_1") (pintype "passive"))
      (node (ref "U5") (pin "3") (pinfunction "A_3") (pintype "passive"))
    )
    (net (code "16") (name "/RADIO_CE") (class "Default")
      (node (ref "CE") (pin "1") (pinfunction "1_1") (pintype "passive"))
      (node (ref "U2") (pin "26") (pinfunction "PA26_26") (pintype "bidirectional"))
      (node (ref "U3") (pin "3") (pinfunction "CE_3") (pintype "passive"))
    )
    (net (code "17") (name "/RADIO_CSN") (class "Default")
      (node (ref "CSN") (pin "1") (pinfunction "1_1") (pintype "passive"))
      (node (ref "U2") (pin "28") (pinfunction "PWMH0/PA11_28") (pintype "bidirectional"))
      (node (ref "U3") (pin "4") (pinfunction "CSN_4") (pintype "passive"))
    )
    (net (code "18") (name "/RADIO_IRQ") (class "Default")
      (node (ref "IRQ") (pin "1") (pinfunction "1_1") (pintype "passive"))
      (node (ref "U2") (pin "20") (pinfunction "PWML3/PA15_20") (pintype "bidirectional"))
      (node (ref "U3") (pin "8") (pinfunction "IRQ_8") (pintype "passive"))
    )
    (net (code "19") (name "/RADIO_MISO") (class "Default")
      (node (ref "MISO") (pin "1") (pinfunction "1_1") (pintype "passive"))
      (node (ref "U2") (pin "27") (pinfunction "MISO/PWMH1/PA12_27") (pintype "bidirectional"))
      (node (ref "U3") (pin "7") (pinfunction "MISO_7") (pintype "passive"))
    )
    (net (code "20") (name "/RADIO_MOSI") (class "Default")
      (node (ref "MOSI") (pin "1") (pinfunction "1_1") (pintype "passive"))
      (node (ref "U2") (pin "22") (pinfunction "MOSI/PWMH2/PA13_22") (pintype "bidirectional"))
      (node (ref "U3") (pin "6") (pinfunction "MOSI_6") (pintype "passive"))
    )
    (net (code "21") (name "/RADIO_SCK") (class "Default")
      (node (ref "SCK") (pin "1") (pinfunction "1_1") (pintype "passive"))
      (node (ref "U2") (pin "21") (pinfunction "SPCK/PWMH3/PA14_21") (pintype "bidirectional"))
      (node (ref "U3") (pin "5") (pinfunction "SCK_5") (pintype "passive"))
    )
    (net (code "22") (name "/STATUS_LED") (class "Default")
      (node (ref "R7") (pin "1") (pinfunction "1_1") (pintype "passive"))
      (node (ref "STAT") (pin "1") (pinfunction "1_1") (pintype "passive"))
      (node (ref "U2") (pin "47") (pinfunction "PWMH1/PA1_47") (pintype "bidirectional"))
    )
    (net (code "23") (name "/SWCLK") (class "Default")
      (node (ref "H2") (pin "2") (pinfunction "2_2") (pintype "passive"))
      (node (ref "SWC") (pin "1") (pinfunction "1_1") (pintype "passive"))
      (node (ref "U2") (pin "53") (pinfunction "PB7/SWCLK/TCK_53") (pintype "bidirectional"))
    )
    (net (code "24") (name "/SWDIO") (class "Default")
      (node (ref "H2") (pin "4") (pinfunction "4_4") (pintype "passive"))
      (node (ref "SWD") (pin "1") (pinfunction "1_1") (pintype "passive"))
      (node (ref "U2") (pin "51") (pinfunction "PB6/SWDIO/TMS_51") (pintype "bidirectional"))
    )
    (net (code "25") (name "/USB_DETECT") (class "Default")
      (node (ref "R1") (pin "1") (pinfunction "1_1") (pintype "passive"))
      (node (ref "R2") (pin "2") (pinfunction "2_2") (pintype "passive"))
      (node (ref "U2") (pin "52") (pinfunction "PA31_52") (pintype "bidirectional"))
      (node (ref "USB") (pin "1") (pinfunction "1_1") (pintype "passive"))
    )
    (net (code "26") (name "/nCH0") (class "Default")
      (node (ref "CH0") (pin "1") (pinfunction "1_1") (pintype "passive"))
      (node (ref "P3") (pin "1") (pinfunction "1_1") (pintype "passive"))
      (node (ref "U2") (pin "16") (pinfunction "AD3/PWML1/PA20_16") (pintype "bidirectional"))
    )
    (net (code "27") (name "/nCH1") (class "Default")
      (node (ref "CH1") (pin "1") (pinfunction "1_1") (pintype "passive"))
      (node (ref "P3") (pin "2") (pinfunction "2_2") (pintype "passive"))
      (node (ref "U2") (pin "15") (pinfunction "PWMH0/PA23_15") (pintype "bidirectional"))
    )
    (net (code "28") (name "/nCH2") (class "Default")
      (node (ref "CH2") (pin "1") (pinfunction "1_1") (pintype "passive"))
      (node (ref "P3") (pin "3") (pinfunction "3_3") (pintype "passive"))
      (node (ref "U2") (pin "14") (pinfunction "AD9/TXD1/PA22_14") (pintype "bidirectional"))
    )
    (net (code "29") (name "/nCH3") (class "Default")
      (node (ref "CH3") (pin "1") (pinfunction "1_1") (pintype "passive"))
      (node (ref "P3") (pin "4") (pinfunction "4_4") (pintype "passive"))
      (node (ref "U2") (pin "13") (pinfunction "AD2/PWML0/PA19_13") (pintype "bidirectional"))
    )
    (net (code "30") (name "/nRST") (class "Default")
      (node (ref "H2") (pin "1") (pinfunction "1_1") (pintype "passive"))
      (node (ref "RST") (pin "1") (pinfunction "1_1") (pintype "passive"))
      (node (ref "S2") (pin "2") (pintype "passive"))
      (node (ref "U2") (pin "39") (pinfunction "~{NRST}_39") (pintype "bidirectional"))
    )
    (net (code "31") (name "/nSLEEP_BTN") (class "Default")
      (node (ref "S1") (pin "2") (pintype "passive"))
      (node (ref "SLP") (pin "1") (pinfunction "1_1") (pintype "passive"))
      (node (ref "U2") (pin "30") (pinfunction "PA9_30") (pintype "bidirectional"))
    )
    (net (code "32") (name "3V3") (class "Default")
      (node (ref "3V3") (pin "1") (pinfunction "1_1") (pintype "passive"))
      (node (ref "C2") (pin "2") (pinfunction "2_2") (pintype "passive"))
      (node (ref "ER2") (pin "1") (pinfunction "1_1") (pintype "passive"))
      (node (ref "H2") (pin "7") (pinfunction "7_7") (pintype "passive"))
      (node (ref "H2") (pin "8") (pinfunction "8_8") (pintype "passive"))
      (node (ref "P1") (pin "1") (pinfunction "1_1") (pintype "passive"))
      (node (ref "R10") (pin "2") (pinfunction "2_2") (pintype "passive"))
      (node (ref "R11") (pin "2") (pinfunction "2_2") (pintype "passive"))
      (node (ref "R13") (pin "2") (pinfunction "2_2") (pintype "passive"))
      (node (ref "R16") (pin "2") (pinfunction "2_2") (pintype "passive"))
      (node (ref "R17") (pin "2") (pinfunction "2_2") (pintype "passive"))
      (node (ref "R20") (pin "2") (pinfunction "2_2") (pintype "passive"))
      (node (ref "U1") (pin "5") (pinfunction "OUT_5") (pintype "power_in"))
      (node (ref "U6") (pin "22") (pinfunction "nCS_22") (pintype "passive"))
      (node (ref "VR1") (pin "1") (pinfunction "1_1") (pintype "passive"))
      (node (ref "VR1") (pin "4") (pinfunction "1'_4") (pintype "passive"))
    )
    (net (code "33") (name "5V") (class "Default")
      (node (ref "5V") (pin "1") (pinfunction "1_1") (pintype "passive"))
      (node (ref "C22") (pin "2") (pinfunction "2_2") (pintype "passive"))
      (node (ref "C23") (pin "2") (pinfunction "2_2") (pintype "passive"))
      (node (ref "H3") (pin "1") (pinfunction "5V_1") (pintype "passive"))
      (node (ref "L2") (pin "2") (pintype "passive"))
      (node (ref "P1") (pin "3") (pinfunction "3_3") (pintype "passive"))
      (node (ref "P5") (pin "1") (pinfunction "1_1") (pintype "passive"))
      (node (ref "R14") (pin "1") (pinfunction "1_1") (pintype "passive"))
      (node (ref "R15") (pin "1") (pinfunction "1_1") (pintype "passive"))
      (node (ref "R18") (pin "2") (pinfunction "2_2") (pintype "passive"))
      (node (ref "U4") (pin "5") (pinfunction "FB_5") (pintype "input"))
    )
    (net (code "34") (name "GND") (class "Default")
      (node (ref "C1") (pin "1") (pinfunction "1_1") (pintype "passive"))
      (node (ref "C10") (pin "1") (pinfunction "1_1") (pintype "passive"))
      (node (ref "C11") (pin "1") (pinfunction "1_1") (pintype "passive"))
      (node (ref "C12") (pin "1") (pinfunction "1_1") (pintype "passive"))
      (node (ref "C13") (pin "1") (pinfunction "1_1") (pintype "passive"))
      (node (ref "C15") (pin "2") (pinfunction "2_2") (pintype "passive"))
      (node (ref "C17") (pin "1") (pintype "passive"))
      (node (ref "C18") (pin "1") (pinfunction "1_1") (pintype "passive"))
      (node (ref "C19") (pin "1") (pinfunction "1_1") (pintype "passive"))
      (node (ref "C2") (pin "1") (pinfunction "1_1") (pintype "passive"))
      (node (ref "C20") (pin "1") (pinfunction "1_1") (pintype "passive"))
      (node (ref "C21") (pin "1") (pinfunction "1_1") (pintype "passive"))
      (node (ref "C22") (pin "1") (pinfunction "1_1") (pintype "passive"))
      (node (ref "C23") (pin "1") (pinfunction "1_1") (pintype "passive"))
      (node (ref "C24") (pin "1") (pinfunction "1_1") (pintype "passive"))
      (node (ref "C25") (pin "2") (pinfunction "2_2") (pintype "passive"))
      (node (ref "C26") (pin "2") (pinfunction "2_2") (pintype "passive"))
      (node (ref "C3") (pin "1") (pinfunction "1_1") (pintype "passive"))
      (node (ref "C4") (pin "1") (pinfunction "1_1") (pintype "passive"))
      (node (ref "C5") (pin "1") (pinfunction "1_1") (pintype "passive"))
      (node (ref "C6") (pin "1") (pinfunction "1_1") (pintype "passive"))
      (node (ref "C7") (pin "1") (pinfunction "1_1") (pintype "passive"))
      (node (ref "C8") (pin "1") (pinfunction "1_1") (pintype "passive"))
      (node (ref "C9") (pin "1") (pinfunction "1_1") (pintype "passive"))
      (node (ref "D2") (pin "1") (pinfunction "A_1") (pintype "passive"))
      (node (ref "DL1") (pin "1") (pinfunction "K_1") (pintype "passive"))
      (node (ref "DL2") (pin "1") (pinfunction "K_1") (pintype "passive"))
      (node (ref "GND0") (pin "1") (pinfunction "1_1") (pintype "passive"))
      (node (ref "GND1") (pin "1") (pinfunction "1_1") (pintype "passive"))
      (node (ref "GND2") (pin "1") (pinfunction "1_1") (pintype "passive"))
      (node (ref "GND3") (pin "1") (pinfunction "1_1") (pintype "passive"))
      (node (ref "H1") (pin "5") (pinfunction "GND_5") (pintype "passive"))
      (node (ref "H1") (pin "6") (pinfunction "SHLD_6") (pintype "passive"))
      (node (ref "H2") (pin "5") (pinfunction "5_5") (pintype "passive"))
      (node (ref "H2") (pin "6") (pinfunction "6_6") (pintype "passive"))
      (node (ref "H3") (pin "3") (pinfunction "COM_3") (pintype "passive"))
      (node (ref "H4") (pin "1") (pinfunction "GND_1") (pintype "passive"))
      (node (ref "H4") (pin "3") (pinfunction "GND_3") (pintype "passive"))
      (node (ref "P1") (pin "4") (pinfunction "4_4") (pintype "passive"))
      (node (ref "P2") (pin "1") (pinfunction "1_1") (pintype "passive"))
      (node (ref "P2") (pin "2") (pinfunction "2_2") (pintype "passive"))
      (node (ref "P2") (pin "3") (pinfunction "3_3") (pintype "passive"))
      (node (ref "P2") (pin "4") (pinfunction "4_4") (pintype "passive"))
      (node (ref "P4") (pin "1") (pinfunction "1_1") (pintype "passive"))
      (node (ref "Q1") (pin "2") (pinfunction "2_2") (pintype "passive"))
      (node (ref "R2") (pin "1") (pinfunction "1_1") (pintype "passive"))
      (node (ref "R21") (pin "1") (pinfunction "1_1") (pintype "passive"))
      (node (ref "R5") (pin "1") (pinfunction "1_1") (pintype "passive"))
      (node (ref "R9") (pin "1") (pinfunction "1_1") (pintype "passive"))
      (node (ref "S1") (pin "1") (pintype "passive"))
      (node (ref "S2") (pin "1") (pintype "passive"))
      (node (ref "U1") (pin "2") (pinfunction "GND_2") (pintype "power_in"))
      (node (ref "U2") (pin "17") (pinfunction "GND_17") (pintype "power_in"))
      (node (ref "U2") (pin "2") (pinfunction "GND_2") (pintype "power_in"))
      (node (ref "U2") (pin "46") (pinfunction "GND_46") (pintype "power_in"))
      (node (ref "U2") (pin "60") (pinfunction "GND_60") (pintype "power_in"))
      (node (ref "U3") (pin "2") (pinfunction "GND_2") (pintype "passive"))
      (node (ref "U4") (pin "6") (pinfunction "NC_6") (pintype "passive"))
      (node (ref "U4") (pin "7") (pinfunction "GND_7") (pintype "power_in"))
      (node (ref "U4") (pin "EPAD") (pinfunction "EPAD_EPAD") (pintype "passive"))
      (node (ref "U5") (pin "2") (pinfunction "GND_2") (pintype "passive"))
      (node (ref "U5") (pin "5") (pinfunction "DIR_5") (pintype "passive"))
      (node (ref "U6") (pin "11") (pinfunction "FSYNC_11") (pintype "passive"))
      (node (ref "U6") (pin "18") (pinfunction "GND_18") (pintype "passive"))
      (node (ref "U6") (pin "20") (pinfunction "RESV_GND_20") (pintype "passive"))
      (node (ref "U6") (pin "9") (pinfunction "AD0/SDO_9") (pintype "passive"))
      (node (ref "VR1") (pin "10") (pinfunction "10_10") (pintype "passive"))
      (node (ref "VR1") (pin "3") (pinfunction "3_3") (pintype "passive"))
      (node (ref "VR1") (pin "6") (pinfunction "3'_6") (pintype "passive"))
      (node (ref "VR1") (pin "7") (pinfunction "7_7") (pintype "passive"))
    )
    (net (code "35") (name "Net-(C14-Pad1)") (class "Default")
      (node (ref "C14") (pin "1") (pinfunction "1_1") (pintype "passive"))
      (node (ref "R5") (pin "2") (pinfunction "2_2") (pintype "passive"))
    )
    (net (code "36") (name "Net-(D2-K)") (class "Default")
      (node (ref "C16") (pin "1") (pinfunction "1_1") (pintype "passive"))
      (node (ref "D2") (pin "2") (pinfunction "K_2") (pintype "passive"))
      (node (ref "L2") (pin "1") (pintype "passive"))
      (node (ref "U4") (pin "8") (pinfunction "SW_8") (pintype "output"))
    )
    (net (code "37") (name "Net-(DL1-A)") (class "Default")
      (node (ref "DL1") (pin "2") (pinfunction "A_2") (pintype "passive"))
      (node (ref "R7") (pin "2") (pinfunction "2_2") (pintype "passive"))
    )
    (net (code "38") (name "Net-(DL2-A)") (class "Default")
      (node (ref "DL2") (pin "2") (pinfunction "A_2") (pintype "passive"))
      (node (ref "R6") (pin "2") (pinfunction "2_2") (pintype "passive"))
    )
    (net (code "39") (name "Net-(F1-Pad2)") (class "Default")
      (node (ref "F1") (pin "2") (pinfunction "2_2") (pintype "passive"))
      (node (ref "Q2") (pin "3") (pinfunction "3_3") (pintype "passive"))
    )
    (net (code "40") (name "Net-(H4-VBATT)") (class "Default")
      (node (ref "C17") (pin "2") (pintype "passive"))
      (node (ref "F1") (pin "1") (pinfunction "1_1") (pintype "passive"))
      (node (ref "H4") (pin "2") (pinfunction "VBATT_2") (pintype "passive"))
      (node (ref "RAW") (pin "1") (pinfunction "1_1") (pintype "passive"))
    )
    (net (code "41") (name "Net-(L3-Pad2)") (class "Default")
      (node (ref "L3") (pin "2") (pinfunction "2_2") (pintype "passive"))
      (node (ref "R10") (pin "1") (pinfunction "1_1") (pintype "passive"))
    )
    (net (code "42") (name "Net-(P5-Pad2)") (class "Default")
      (node (ref "P5") (pin "2") (pinfunction "2_2") (pintype "passive"))
      (node (ref "Q1") (pin "3") (pinfunction "3_3") (pintype "passive"))
      (node (ref "R18") (pin "1") (pinfunction "1_1") (pintype "passive"))
    )
    (net (code "43") (name "Net-(Q1-Pad1)") (class "Default")
      (node (ref "Q1") (pin "1") (pinfunction "1_1") (pintype "passive"))
      (node (ref "R19") (pin "1") (pinfunction "1_1") (pintype "passive"))
    )
    (net (code "44") (name "Net-(Q2-Pad1)") (class "Default")
      (node (ref "Q2") (pin "1") (pinfunction "1_1") (pintype "passive"))
      (node (ref "R21") (pin "2") (pinfunction "2_2") (pintype "passive"))
    )
    (net (code "45") (name "Net-(U1-EN)") (class "Default")
      (node (ref "C1") (pin "2") (pinfunction "2_2") (pintype "passive"))
      (node (ref "R14") (pin "2") (pinfunction "2_2") (pintype "passive"))
      (node (ref "U1") (pin "1") (pinfunction "IN_1") (pintype "power_in"))
      (node (ref "U1") (pin "3") (pinfunction "EN_3") (pintype "input"))
    )
    (net (code "46") (name "Net-(U2A-PB8{slash}XOUT)") (class "Default")
      (node (ref "C4") (pin "2") (pinfunction "2_2") (pintype "passive"))
      (node (ref "U2") (pin "61") (pinfunction "PB8/XOUT_61") (pintype "bidirectional"))
      (node (ref "Y1") (pin "1") (pinfunction "OSC1_1") (pintype "passive"))
    )
    (net (code "47") (name "Net-(U2A-PB9{slash}XIN)") (class "Default")
      (node (ref "C3") (pin "2") (pinfunction "2_2") (pintype "passive"))
      (node (ref "U2") (pin "62") (pinfunction "PB9/XIN_62") (pintype "bidirectional"))
      (node (ref "Y1") (pin "3") (pinfunction "OSC2_3") (pintype "passive"))
    )
    (net (code "48") (name "Net-(U2A-PB10{slash}DDM)") (class "Default")
      (node (ref "R4") (pin "2") (pinfunction "2_2") (pintype "passive"))
      (node (ref "U2") (pin "56") (pinfunction "PB10/DDM_56") (pintype "bidirectional"))
    )
    (net (code "49") (name "Net-(U2A-PB11{slash}DDP)") (class "Default")
      (node (ref "R3") (pin "2") (pinfunction "2_2") (pintype "passive"))
      (node (ref "U2") (pin "57") (pinfunction "PB11/DDP_57") (pintype "bidirectional"))
    )
    (net (code "50") (name "Net-(U2A-PB12{slash}ERASE)") (class "Default")
      (node (ref "ER1") (pin "1") (pinfunction "1_1") (pintype "passive"))
      (node (ref "U2") (pin "55") (pinfunction "PB12/ERASE_55") (pintype "bidirectional"))
    )
    (net (code "51") (name "Net-(U2B-ADVREF)") (class "Default")
      (node (ref "C11") (pin "2") (pinfunction "2_2") (pintype "passive"))
      (node (ref "C13") (pin "2") (pinfunction "2_2") (pintype "passive"))
      (node (ref "C5") (pin "2") (pinfunction "2_2") (pintype "passive"))
      (node (ref "C7") (pin "2") (pinfunction "2_2") (pintype "passive"))
      (node (ref "C9") (pin "2") (pinfunction "2_2") (pintype "passive"))
      (node (ref "R11") (pin "1") (pinfunction "1_1") (pintype "passive"))
      (node (ref "U2") (pin "1") (pinfunction "ADVREF_1") (pintype "input"))
      (node (ref "U2") (pin "18") (pinfunction "VDDIO_18") (pintype "power_in"))
      (node (ref "U2") (pin "45") (pinfunction "VDDIO_45") (pintype "power_in"))
      (node (ref "U2") (pin "58") (pinfunction "VDDIO_58") (pintype "power_in"))
      (node (ref "U2") (pin "7") (pinfunction "VDDIN_7") (pintype "power_in"))
    )
    (net (code "52") (name "Net-(U2B-VDDOUT)") (class "Default")
      (node (ref "C10") (pin "2") (pinfunction "2_2") (pintype "passive"))
      (node (ref "C12") (pin "2") (pinfunction "2_2") (pintype "passive"))
      (node (ref "C6") (pin "2") (pinfunction "2_2") (pintype "passive"))
      (node (ref "C8") (pin "2") (pinfunction "2_2") (pintype "passive"))
      (node (ref "COR") (pin "1") (pinfunction "1_1") (pintype "passive"))
      (node (ref "L1") (pin "2") (pinfunction "2_2") (pintype "passive"))
      (node (ref "U2") (pin "12") (pinfunction "VDDCORE_12") (pintype "power_in"))
      (node (ref "U2") (pin "24") (pinfunction "VDDCORE_24") (pintype "power_in"))
      (node (ref "U2") (pin "54") (pinfunction "VDDCORE_54") (pintype "power_in"))
      (node (ref "U2") (pin "8") (pinfunction "VDDOUT_8") (pintype "power_in"))
    )
    (net (code "53") (name "Net-(U2B-VDDPLL)") (class "Default")
      (node (ref "C14") (pin "2") (pinfunction "2_2") (pintype "passive"))
      (node (ref "C15") (pin "1") (pinfunction "1_1") (pintype "passive"))
      (node (ref "L1") (pin "1") (pinfunction "1_1") (pintype "passive"))
      (node (ref "PLL") (pin "1") (pinfunction "1_1") (pintype "passive"))
      (node (ref "U2") (pin "64") (pinfunction "VDDPLL_64") (pintype "power_in"))
    )
    (net (code "54") (name "Net-(U3-VCC)") (class "Default")
      (node (ref "C18") (pin "2") (pinfunction "2_2") (pintype "passive"))
      (node (ref "L3") (pin "1") (pinfunction "1_1") (pintype "passive"))
      (node (ref "U3") (pin "1") (pinfunction "VCC_1") (pintype "passive"))
    )
    (net (code "55") (name "Net-(U4-BST)") (class "Default")
      (node (ref "C16") (pin "2") (pinfunction "2_2") (pintype "passive"))
      (node (ref "U4") (pin "1") (pinfunction "BST_1") (pintype "passive"))
    )
    (net (code "56") (name "Net-(U4-EN)") (class "Default")
      (node (ref "C21") (pin "2") (pinfunction "2_2") (pintype "passive"))
      (node (ref "R12") (pin "2") (pinfunction "2_2") (pintype "passive"))
      (node (ref "U4") (pin "2") (pinfunction "VIN_2") (pintype "input"))
      (node (ref "U4") (pin "3") (pinfunction "EN_3") (pintype "input"))
    )
    (net (code "57") (name "Net-(U5-VCCA)") (class "Default")
      (node (ref "C19") (pin "2") (pinfunction "2_2") (pintype "passive"))
      (node (ref "R15") (pin "2") (pinfunction "2_2") (pintype "passive"))
      (node (ref "U5") (pin "1") (pinfunction "VCCA_1") (pintype "passive"))
    )
    (net (code "58") (name "Net-(U5-VCCB)") (class "Default")
      (node (ref "C20") (pin "2") (pinfunction "2_2") (pintype "passive"))
      (node (ref "R16") (pin "1") (pinfunction "1_1") (pintype "passive"))
      (node (ref "U5") (pin "6") (pinfunction "VCCB_6") (pintype "passive"))
    )
    (net (code "59") (name "Net-(U6-REGOUT)") (class "Default")
      (node (ref "C26") (pin "1") (pinfunction "1_1") (pintype "passive"))
      (node (ref "U6") (pin "10") (pinfunction "REGOUT_10") (pintype "passive"))
    )
    (net (code "60") (name "Net-(U6-RESV_VDDIO)") (class "Default")
      (node (ref "C24") (pin "2") (pinfunction "2_2") (pintype "passive"))
      (node (ref "C25") (pin "1") (pinfunction "1_1") (pintype "passive"))
      (node (ref "R17") (pin "1") (pinfunction "1_1") (pintype "passive"))
      (node (ref "U6") (pin "1") (pinfunction "RESV_VDDIO_1") (pintype "passive"))
      (node (ref "U6") (pin "13") (pinfunction "VDD_13") (pintype "passive"))
      (node (ref "U6") (pin "8") (pinfunction "VDDIO_8") (pintype "passive"))
    )
    (net (code "61") (name "VBAT") (class "Default")
      (node (ref "Q2") (pin "2") (pinfunction "2_2") (pintype "passive"))
      (node (ref "R12") (pin "1") (pinfunction "1_1") (pintype "passive"))
      (node (ref "R8") (pin "2") (pinfunction "2_2") (pintype "passive"))
      (node (ref "VBAT") (pin "1") (pinfunction "1_1") (pintype "passive"))
    )
    (net (code "62") (name "VBUS") (class "Default")
      (node (ref "BUS") (pin "1") (pinfunction "1_1") (pintype "passive"))
      (node (ref "H1") (pin "1") (pinfunction "VBUS_1") (pintype "power_in"))
      (node (ref "R1") (pin "2") (pinfunction "2_2") (pintype "passive"))
    )
    (net (code "63") (name "unconnected-(H1-ID-Pad4)") (class "Default")
      (node (ref "H1") (pin "4") (pinfunction "ID_4") (pintype "power_in+no_connect"))
    )
    (net (code "64") (name "unconnected-(H2-Pad3)") (class "Default")
      (node (ref "H2") (pin "3") (pinfunction "3_3") (pintype "passive+no_connect"))
    )
    (net (code "65") (name "unconnected-(H2-Pad9)") (class "Default")
      (node (ref "H2") (pin "9") (pinfunction "9_9") (pintype "passive+no_connect"))
    )
    (net (code "66") (name "unconnected-(H2-Pad10)") (class "Default")
      (node (ref "H2") (pin "10") (pinfunction "10_10") (pintype "passive+no_connect"))
    )
    (net (code "67") (name "unconnected-(P4-Pad3)") (class "Default")
      (node (ref "P4") (pin "3") (pinfunction "3_3") (pintype "passive+no_connect"))
    )
    (net (code "68") (name "unconnected-(U1-BYP-Pad4)") (class "Default")
      (node (ref "U1") (pin "4") (pinfunction "BYP_4") (pintype "passive+no_connect"))
    )
    (net (code "69") (name "unconnected-(U2A-AD1{slash}PA18-Pad10)") (class "Default")
      (node (ref "U2") (pin "10") (pinfunction "AD1/PA18_10") (pintype "bidirectional"))
    )
    (net (code "70") (name "unconnected-(U2A-AD8{slash}RXD1{slash}PA21-Pad11)") (class "Default")
      (node (ref "U2") (pin "11") (pinfunction "AD8/RXD1/PA21_11") (pintype "bidirectional"))
    )
    (net (code "71") (name "unconnected-(U2A-JTAGSEL-Pad50)") (class "Default")
      (node (ref "U2") (pin "50") (pinfunction "JTAGSEL_50") (pintype "input+no_connect"))
    )
    (net (code "72") (name "unconnected-(U2A-PA10-Pad29)") (class "Default")
      (node (ref "U2") (pin "29") (pinfunction "PA10_29") (pintype "bidirectional"))
    )
    (net (code "73") (name "unconnected-(U2A-PA28-Pad38)") (class "Default")
      (node (ref "U2") (pin "38") (pinfunction "PA28_38") (pintype "bidirectional"))
    )
    (net (code "74") (name "unconnected-(U2A-PA29-Pad41)") (class "Default")
      (node (ref "U2") (pin "41") (pinfunction "PA29_41") (pintype "bidirectional"))
    )
    (net (code "75") (name "unconnected-(U2A-PB3{slash}AD7-Pad6)") (class "Default")
      (node (ref "U2") (pin "6") (pinfunction "PB3/AD7_6") (pintype "bidirectional+no_connect"))
    )
    (net (code "76") (name "unconnected-(U2A-PB4{slash}PWMH2{slash}TDI-Pad33)") (class "Default")
      (node (ref "U2") (pin "33") (pinfunction "PB4/PWMH2/TDI_33") (pintype "bidirectional+no_connect"))
    )
    (net (code "77") (name "unconnected-(U2A-PB5{slash}PWML0{slash}TDO-Pad49)") (class "Default")
      (node (ref "U2") (pin "49") (pinfunction "PB5/PWML0/TDO_49") (pintype "bidirectional+no_connect"))
    )
    (net (code "78") (name "unconnected-(U2A-PB13{slash}PWML2{slash}DAC0-Pad59)") (class "Default")
      (node (ref "U2") (pin "59") (pinfunction "PB13/PWML2/DAC0_59") (pintype "bidirectional+no_connect"))
    )
    (net (code "79") (name "unconnected-(U2A-PB14{slash}PWMH3{slash}DAC1-Pad63)") (class "Default")
      (node (ref "U2") (pin "63") (pinfunction "PB14/PWMH3/DAC1_63") (pintype "bidirectional+no_connect"))
    )
    (net (code "80") (name "unconnected-(U2A-PWMH1{slash}PA24-Pad23)") (class "Default")
      (node (ref "U2") (pin "23") (pinfunction "PWMH1/PA24_23") (pintype "bidirectional"))
    )
    (net (code "81") (name "unconnected-(U2A-PWMH2{slash}PA25-Pad25)") (class "Default")
      (node (ref "U2") (pin "25") (pinfunction "PWMH2/PA25_25") (pintype "bidirectional"))
    )
    (net (code "82") (name "unconnected-(U2A-PWML2{slash}PA16-Pad19)") (class "Default")
      (node (ref "U2") (pin "19") (pinfunction "PWML2/PA16_19") (pintype "bidirectional+no_connect"))
    )
    (net (code "83") (name "unconnected-(U2A-PWML2{slash}PA30-Pad42)") (class "Default")
      (node (ref "U2") (pin "42") (pinfunction "PWML2/PA30_42") (pintype "bidirectional"))
    )
    (net (code "84") (name "unconnected-(U2A-RXD0{slash}PA5-Pad35)") (class "Default")
      (node (ref "U2") (pin "35") (pinfunction "RXD0/PA5_35") (pintype "bidirectional"))
    )
    (net (code "85") (name "unconnected-(U2A-TST-Pad40)") (class "Default")
      (node (ref "U2") (pin "40") (pinfunction "TST_40") (pintype "input+no_connect"))
    )
    (net (code "86") (name "unconnected-(U4-PGOOD-Pad4)") (class "Default")
      (node (ref "U4") (pin "4") (pinfunction "PGOOD_4") (pintype "output+no_connect"))
    )
    (net (code "87") (name "unconnected-(U6-AUX_CL-Pad7)") (class "Default")
      (node (ref "U6") (pin "7") (pinfunction "AUX_CL_7") (pintype "passive+no_connect"))
    )
    (net (code "88") (name "unconnected-(U6-AUX_DA-Pad21)") (class "Default")
      (node (ref "U6") (pin "21") (pinfunction "AUX_DA_21") (pintype "passive+no_connect"))
    )
  )
)
